# POWER.net
KiCad netlist of a schematic drawn in Altium Designer
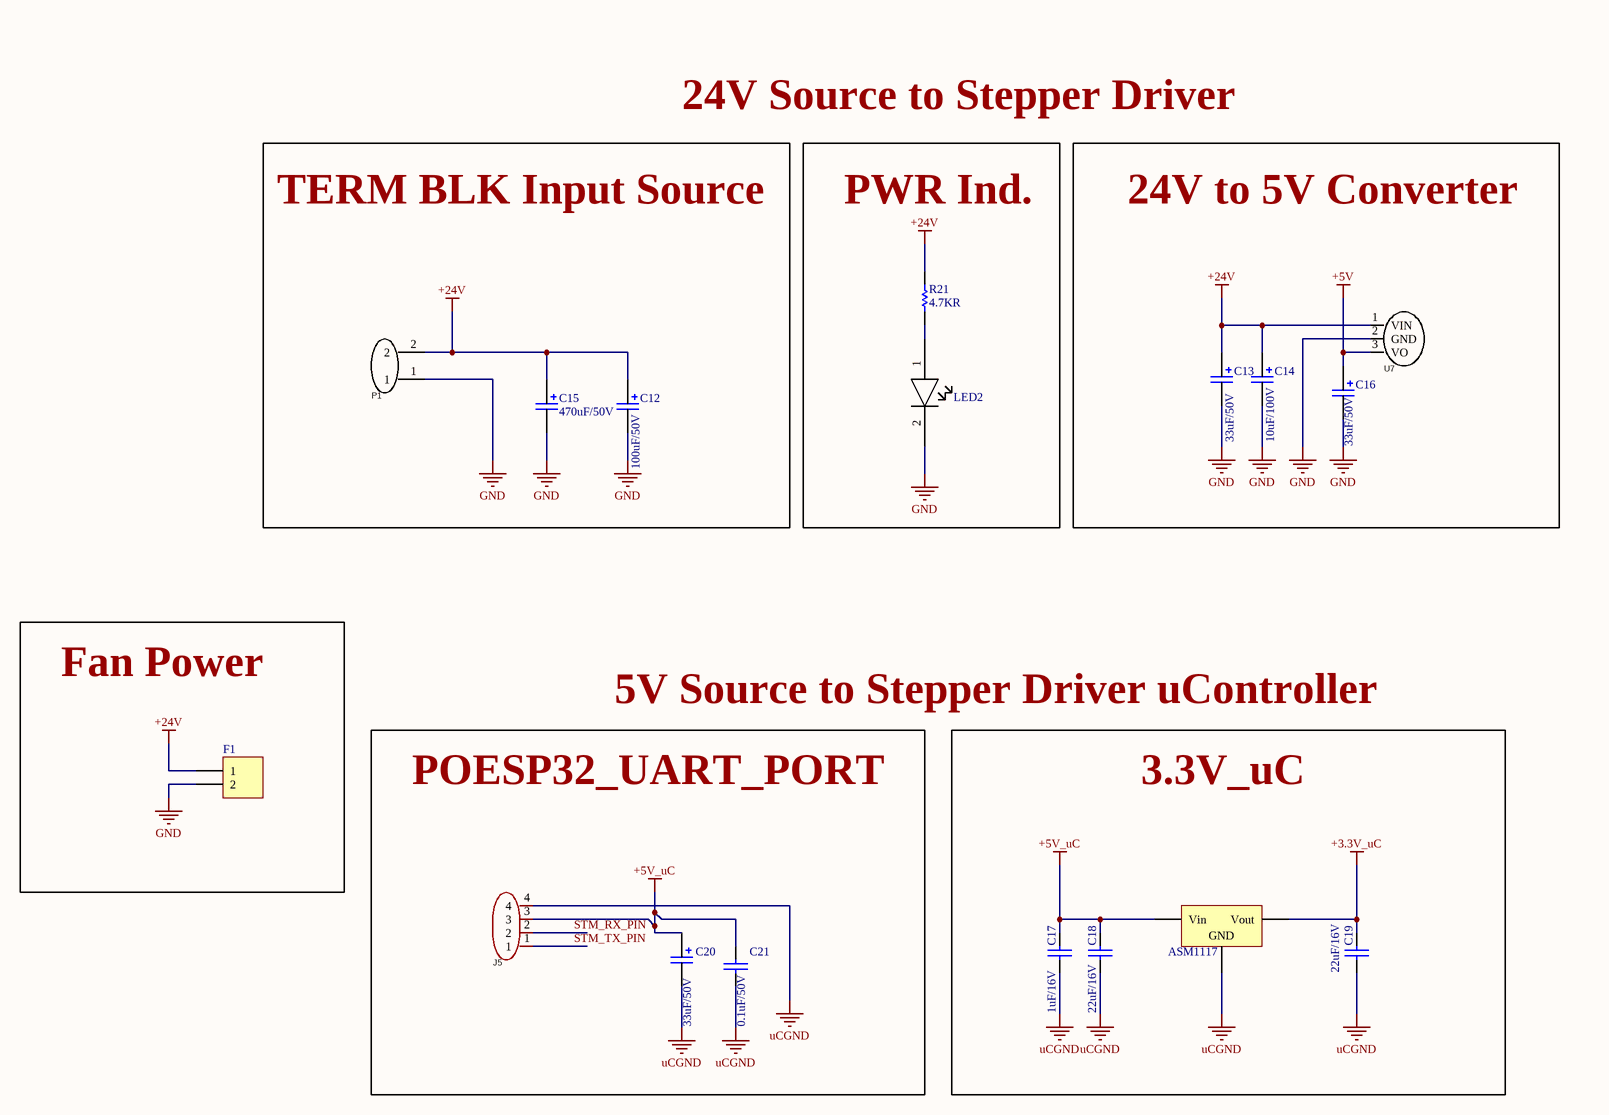
[diagram p0: POWER.SchDoc]

(export (version "E")
  (design (tool "Eeschema 10.0.6"))
  (components
    (comp (ref "ASM1117")
      (value "AMS1117 - 3.3V Reg")
      (footprint "SOT229P700X180-4N")
      (description "C347222")
      (fields (field (name "CREATED BY") "NourAldin"))
      (libsource (lib "AMS1117 - 3.3V Reg") (part "AMS1117 - 3.3V Reg"))
    )
    (comp (ref "C12")
      (value "100uF/50V")
      (footprint "CAPLEAD_D6.3mm")
      (description "C47891")
      (fields
        (field (name "MANUFACTURER") "KEMET")
        (field (name "MANUFACTURER PART NUMBER") "A759EQ475M2AAAE160")
      )
      (libsource (lib "GlobalLib") (part "A759EQ475M2AAAE160"))
    )
    (comp (ref "C13")
      (value "33uF/50V")
      (footprint "CAPLEAD_D6.3mm")
      (description "C45099")
      (fields
        (field (name "MANUFACTURER") "KEMET")
        (field (name "MANUFACTURER PART NUMBER") "A759EQ475M2AAAE160")
      )
      (libsource (lib "GlobalLib") (part "A759EQ475M2AAAE160"))
    )
    (comp (ref "C14")
      (value "10uF/100V")
      (footprint "CAPLEAD_D6.3mm")
      (description "C2029")
      (fields
        (field (name "MANUFACTURER") "KEMET")
        (field (name "MANUFACTURER PART NUMBER") "A759EQ475M2AAAE160")
      )
      (libsource (lib "GlobalLib") (part "A759EQ475M2AAAE160"))
    )
    (comp (ref "C15")
      (value "470uF/50V")
      (footprint "CAPLEAD_D10mm")
      (description "C2960279")
      (fields
        (field (name "MANUFACTURER") "Vishay BCcomponents")
        (field (name "MANUFACTURER PART NUMBER") "MAL215058101E3")
      )
      (libsource (lib "GlobalLib") (part "MAL215058101E3"))
    )
    (comp (ref "C16")
      (value "33uF/50V")
      (footprint "CAPLEAD_D6.3mm")
      (description "C45099")
      (fields
        (field (name "MANUFACTURER") "KEMET")
        (field (name "MANUFACTURER PART NUMBER") "A759EQ475M2AAAE160")
      )
      (libsource (lib "GlobalLib") (part "A759EQ475M2AAAE160"))
    )
    (comp (ref "C17")
      (value "1uF/16V")
      (footprint "PCBComponent_1")
      (description "C1592")
      (fields (field (name "CREATED BY") "NourAldin"))
      (libsource (lib "0603 Capacitor") (part "0603 Capacitor"))
    )
    (comp (ref "C18")
      (value "22uF/16V")
      (footprint "PCBComponent_1")
      (description "C2762594")
      (fields (field (name "CREATED BY") "NourAldin"))
      (libsource (lib "0603 Capacitor") (part "0603 Capacitor"))
    )
    (comp (ref "C19")
      (value "22uF/16V")
      (footprint "PCBComponent_1")
      (description "C2762594")
      (fields (field (name "CREATED BY") "NourAldin"))
      (libsource (lib "0603 Capacitor") (part "0603 Capacitor"))
    )
    (comp (ref "C20")
      (value "33uF/50V")
      (footprint "CAPLEAD_D6.3mm")
      (description "C45099")
      (fields
        (field (name "MANUFACTURER") "KEMET")
        (field (name "MANUFACTURER PART NUMBER") "A759EQ475M2AAAE160")
      )
      (libsource (lib "GlobalLib") (part "A759EQ475M2AAAE160"))
    )
    (comp (ref "C21")
      (value "0.1uF/50V")
      (footprint "PCBComponent_1")
      (description "C1591")
      (fields (field (name "CREATED BY") "NourAldin"))
      (libsource (lib "0603 Capacitor") (part "0603 Capacitor"))
    )
    (comp (ref "F1")
      (value "~")
      (footprint "PinHeader Polar")
      (description "C492401")
      (fields (field (name "CREATED BY") "NourAldin"))
      (libsource (lib "Header 2 pin") (part "Header 2 pin"))
    )
    (comp (ref "J5")
      (value "Header 4P*2mm")
      (footprint "CONN-TH_4P-P2.00_HX20020-4A_2")
      (description "C42372479")
      (fields (field (name "MANUFACTURER") "Megastar(兆星)") (field (name "MANUFACTURER PART") "ZX-HY2.0-4PZZ"))
      (libsource (lib "LIB") (part "ZX-HY2.0-4PZZ"))
    )
    (comp (ref "LED2")
      (value "1206 LED")
      (footprint "1206 LED")
      (description "C434442")
      (fields (field (name "CREATED BY") "NourAldin"))
      (libsource (lib "1206 LED") (part "1206 LED"))
    )
    (comp (ref "P1")
      (value "WJ45C-B-9.5-2P")
      (footprint "CONN-TH_2P-P9.50_WJ45C-B-2P")
      (description "C8397")
      (fields (field (name "MANUFACTURER") "KANGNEX(康奈克斯电气)"))
      (libsource (lib "LIB") (part "WJ45C-B-9.5-2P"))
    )
    (comp (ref "R21")
      (value "4.7KR")
      (footprint "R0402")
      (description "C105871")
      (libsource (lib "DIVERSE") (part "0402 Resistor"))
    )
    (comp (ref "U7")
      (value "C5369649")
      (footprint "SIP-3")
      (fields (field (name "MANUFACTURER") "YLPTEC(易川)") (field (name "MANUFACTURER PART") "K7805M-1000R3"))
      (libsource (lib "LIB") (part "K7805M-1000R3_C5369649"))
    )
  )
  (nets
    (net (code "1") (name "+3.3V_uC") (class "Default")
      (node (ref "ASM1117") (pin "Vout") (pinfunction "Vout_Vout") (pintype "passive"))
      (node (ref "C19") (pin "2") (pinfunction "2_2") (pintype "passive"))
    )
    (net (code "2") (name "+5V") (class "Default")
      (node (ref "C16") (pin "1") (pinfunction "1_1") (pintype "passive"))
      (node (ref "U7") (pin "3") (pinfunction "VO_3") (pintype "passive"))
    )
    (net (code "3") (name "+5V_uC") (class "Default")
      (node (ref "ASM1117") (pin "Vin") (pinfunction "Vin_Vin") (pintype "passive"))
      (node (ref "C17") (pin "2") (pinfunction "2_2") (pintype "passive"))
      (node (ref "C18") (pin "2") (pinfunction "2_2") (pintype "passive"))
      (node (ref "C20") (pin "1") (pinfunction "1_1") (pintype "passive"))
      (node (ref "C21") (pin "2") (pinfunction "2_2") (pintype "passive"))
      (node (ref "J5") (pin "3") (pinfunction "3_3") (pintype "passive"))
    )
    (net (code "4") (name "+24V") (class "Default")
      (node (ref "C12") (pin "1") (pinfunction "1_1") (pintype "passive"))
      (node (ref "C13") (pin "1") (pinfunction "1_1") (pintype "passive"))
      (node (ref "C14") (pin "1") (pinfunction "1_1") (pintype "passive"))
      (node (ref "C15") (pin "1") (pinfunction "1_1") (pintype "passive"))
      (node (ref "F1") (pin "1") (pinfunction "1_1") (pintype "passive"))
      (node (ref "P1") (pin "2") (pinfunction "2_2") (pintype "passive"))
      (node (ref "R21") (pin "1") (pinfunction "1_1") (pintype "passive"))
      (node (ref "U7") (pin "1") (pinfunction "VIN_1") (pintype "passive"))
    )
    (net (code "5") (name "/STM_RX_PIN") (class "Default")
      (node (ref "J5") (pin "2") (pinfunction "2_2") (pintype "passive"))
    )
    (net (code "6") (name "/STM_TX_PIN") (class "Default")
      (node (ref "J5") (pin "1") (pinfunction "1_1") (pintype "passive"))
    )
    (net (code "7") (name "GND") (class "Default")
      (node (ref "C12") (pin "2") (pinfunction "2_2") (pintype "passive"))
      (node (ref "C13") (pin "2") (pinfunction "2_2") (pintype "passive"))
      (node (ref "C14") (pin "2") (pinfunction "2_2") (pintype "passive"))
      (node (ref "C15") (pin "2") (pinfunction "2_2") (pintype "passive"))
      (node (ref "C16") (pin "2") (pinfunction "2_2") (pintype "passive"))
      (node (ref "F1") (pin "2") (pinfunction "2_2") (pintype "passive"))
      (node (ref "LED2") (pin "2") (pinfunction "2_2") (pintype "passive"))
      (node (ref "P1") (pin "1") (pinfunction "1_1") (pintype "passive"))
      (node (ref "U7") (pin "2") (pinfunction "GND_2") (pintype "passive"))
    )
    (net (code "8") (name "Net-(LED2-Pad1)") (class "Default")
      (node (ref "LED2") (pin "1") (pinfunction "1_1") (pintype "passive"))
      (node (ref "R21") (pin "2") (pinfunction "2_2") (pintype "passive"))
    )
    (net (code "9") (name "uCGND") (class "Default")
      (node (ref "ASM1117") (pin "GND") (pinfunction "GND_GND") (pintype "passive"))
      (node (ref "C17") (pin "1") (pinfunction "1_1") (pintype "passive"))
      (node (ref "C18") (pin "1") (pinfunction "1_1") (pintype "passive"))
      (node (ref "C19") (pin "1") (pinfunction "1_1") (pintype "passive"))
      (node (ref "C20") (pin "2") (pinfunction "2_2") (pintype "passive"))
      (node (ref "C21") (pin "1") (pinfunction "1_1") (pintype "passive"))
      (node (ref "J5") (pin "4") (pinfunction "4_4") (pintype "passive"))
    )
  )
)
